# Legendre.net
KiCad netlist of a schematic drawn in Altium Designer
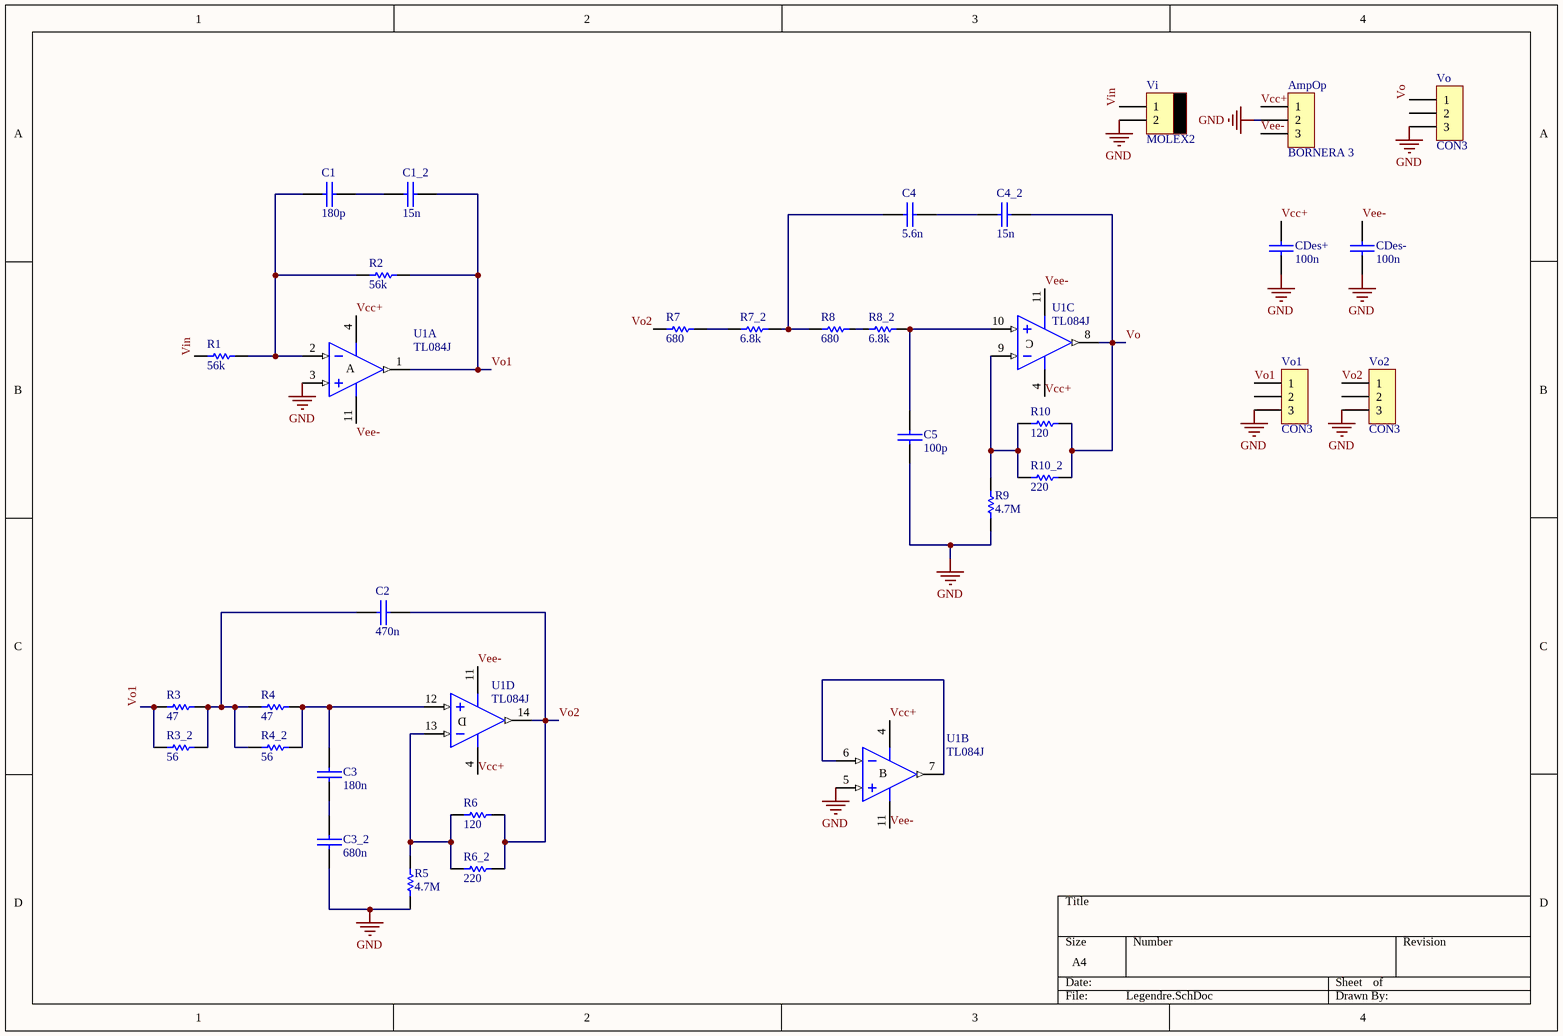
[diagram p0: Legendre.SchDoc]

(export (version "E")
  (design (tool "Eeschema 10.0.6"))
  (components
    (comp (ref "AmpOp")
      (value "BORNERA 3")
      (footprint "BORNERA3")
      (libsource (lib "LIBEBAL") (part "BORNERA 3"))
    )
    (comp (ref "C1") (value "180p") (footprint "0805") (libsource (lib "LIBEBAL") (part "CAP")))
    (comp (ref "C1_2") (value "15n") (footprint "0805") (libsource (lib "LIBEBAL") (part "CAP")))
    (comp (ref "C2") (value "470n") (footprint "0805") (libsource (lib "LIBEBAL") (part "CAP")))
    (comp (ref "C3") (value "180n") (footprint "0805") (libsource (lib "LIBEBAL") (part "CAP")))
    (comp (ref "C3_2") (value "680n") (footprint "CAP100") (libsource (lib "LIBEBAL") (part "CAP")))
    (comp (ref "C4") (value "5.6n") (footprint "0805") (libsource (lib "LIBEBAL") (part "CAP")))
    (comp (ref "C4_2") (value "15n") (footprint "0805") (libsource (lib "LIBEBAL") (part "CAP")))
    (comp (ref "C5") (value "100p") (footprint "CAP100") (libsource (lib "LIBEBAL") (part "CAP")))
    (comp (ref "CDes+") (value "100n") (footprint "CAP100") (libsource (lib "LIBEBAL") (part "CAP")))
    (comp (ref "CDes-") (value "100n") (footprint "CAP100") (libsource (lib "LIBEBAL") (part "CAP")))
    (comp (ref "R1") (value "56k") (footprint "0805") (libsource (lib "LIBEBAL") (part "RES")))
    (comp (ref "R2") (value "56k") (footprint "0805") (libsource (lib "LIBEBAL") (part "RES")))
    (comp (ref "R3") (value "47") (footprint "0805") (libsource (lib "LIBEBAL") (part "RES")))
    (comp (ref "R3_2") (value "56") (footprint "0805") (libsource (lib "LIBEBAL") (part "RES")))
    (comp (ref "R4") (value "47") (footprint "0805") (libsource (lib "LIBEBAL") (part "RES")))
    (comp (ref "R4_2") (value "56") (footprint "0805") (libsource (lib "LIBEBAL") (part "RES")))
    (comp (ref "R5") (value "4.7M") (footprint "0805") (libsource (lib "LIBEBAL") (part "RES")))
    (comp (ref "R6") (value "120") (footprint "0805") (libsource (lib "LIBEBAL") (part "RES")))
    (comp (ref "R6_2") (value "220") (footprint "0805") (libsource (lib "LIBEBAL") (part "RES")))
    (comp (ref "R7") (value "680") (footprint "0805") (libsource (lib "LIBEBAL") (part "RES")))
    (comp (ref "R7_2") (value "6.8k") (footprint "0805") (libsource (lib "LIBEBAL") (part "RES")))
    (comp (ref "R8") (value "680") (footprint "0805") (libsource (lib "LIBEBAL") (part "RES")))
    (comp (ref "R8_2") (value "6.8k") (footprint "0805") (libsource (lib "LIBEBAL") (part "RES")))
    (comp (ref "R9") (value "4.7M") (footprint "0805") (libsource (lib "LIBEBAL") (part "RES")))
    (comp (ref "R10") (value "120") (footprint "0805") (libsource (lib "LIBEBAL") (part "RES")))
    (comp (ref "R10_2") (value "220") (footprint "0805") (libsource (lib "LIBEBAL") (part "RES")))
    (comp (ref "U1")
      (value "TL084J")
      (footprint "J014")
      (description "JFET-Input Operational Amplifier")
      (fields (field (name "PUBLISHER") "Altium Limited"))
      (libsource (lib "TI Operational Amplifier") (part "TL084J"))
    )
    (comp (ref "Vi") (value "MOLEX2") (footprint "MOLEX2") (libsource (lib "LIBEBAL") (part "MOLEX2")))
    (comp (ref "Vo") (value "CON3") (footprint "SIP3") (libsource (lib "LIBEBAL") (part "CON3")))
    (comp (ref "Vo1") (value "CON3") (footprint "SIP3") (libsource (lib "LIBEBAL") (part "CON3")))
    (comp (ref "Vo2") (value "CON3") (footprint "SIP3") (libsource (lib "LIBEBAL") (part "CON3")))
  )
  (nets
    (net (code "1") (name "/Vcc+") (class "Default")
      (node (ref "AmpOp") (pin "1") (pinfunction "1_1") (pintype "passive"))
      (node (ref "CDes+") (pin "1") (pinfunction "1_1") (pintype "passive"))
      (node (ref "U1") (pin "4") (pinfunction "V+_4") (pintype "power_in"))
    )
    (net (code "2") (name "/Vee-") (class "Default")
      (node (ref "AmpOp") (pin "3") (pinfunction "3_3") (pintype "passive"))
      (node (ref "CDes-") (pin "1") (pinfunction "1_1") (pintype "passive"))
      (node (ref "U1") (pin "11") (pinfunction "V-_11") (pintype "power_in"))
    )
    (net (code "3") (name "/Vin") (class "Default")
      (node (ref "R1") (pin "1") (pinfunction "1_1") (pintype "passive"))
      (node (ref "Vi") (pin "1") (pinfunction "1_1") (pintype "passive"))
    )
    (net (code "4") (name "/Vo") (class "Default")
      (node (ref "C4_2") (pin "2") (pinfunction "2_2") (pintype "passive"))
      (node (ref "R10") (pin "2") (pinfunction "2_2") (pintype "passive"))
      (node (ref "R10_2") (pin "2") (pinfunction "2_2") (pintype "passive"))
      (node (ref "U1") (pin "8") (pinfunction "OUT_8") (pintype "output"))
      (node (ref "Vo") (pin "1") (pinfunction "1_1") (pintype "passive"))
    )
    (net (code "5") (name "/Vo1") (class "Default")
      (node (ref "C1_2") (pin "2") (pinfunction "2_2") (pintype "passive"))
      (node (ref "R2") (pin "2") (pinfunction "2_2") (pintype "passive"))
      (node (ref "R3") (pin "1") (pinfunction "1_1") (pintype "passive"))
      (node (ref "R3_2") (pin "1") (pinfunction "1_1") (pintype "passive"))
      (node (ref "U1") (pin "1") (pinfunction "OUT_1") (pintype "output"))
      (node (ref "Vo1") (pin "1") (pinfunction "1_1") (pintype "passive"))
    )
    (net (code "6") (name "/Vo2") (class "Default")
      (node (ref "C2") (pin "2") (pinfunction "2_2") (pintype "passive"))
      (node (ref "R6") (pin "2") (pinfunction "2_2") (pintype "passive"))
      (node (ref "R6_2") (pin "2") (pinfunction "2_2") (pintype "passive"))
      (node (ref "R7") (pin "1") (pinfunction "1_1") (pintype "passive"))
      (node (ref "U1") (pin "14") (pinfunction "OUT_14") (pintype "output"))
      (node (ref "Vo2") (pin "1") (pinfunction "1_1") (pintype "passive"))
    )
    (net (code "7") (name "GND") (class "Default")
      (node (ref "AmpOp") (pin "2") (pinfunction "2_2") (pintype "passive"))
      (node (ref "C3_2") (pin "2") (pinfunction "2_2") (pintype "passive"))
      (node (ref "C5") (pin "2") (pinfunction "2_2") (pintype "passive"))
      (node (ref "CDes+") (pin "2") (pinfunction "2_2") (pintype "passive"))
      (node (ref "CDes-") (pin "2") (pinfunction "2_2") (pintype "passive"))
      (node (ref "R5") (pin "1") (pinfunction "1_1") (pintype "passive"))
      (node (ref "R9") (pin "1") (pinfunction "1_1") (pintype "passive"))
      (node (ref "U1") (pin "3") (pinfunction "IN+_3") (pintype "input"))
      (node (ref "U1") (pin "5") (pinfunction "IN+_5") (pintype "input"))
      (node (ref "Vi") (pin "2") (pinfunction "2_2") (pintype "passive"))
      (node (ref "Vo") (pin "3") (pinfunction "3_3") (pintype "passive"))
      (node (ref "Vo1") (pin "3") (pinfunction "3_3") (pintype "passive"))
      (node (ref "Vo2") (pin "3") (pinfunction "3_3") (pintype "passive"))
    )
    (net (code "8") (name "Net-(C1-Pad2)") (class "Default")
      (node (ref "C1") (pin "2") (pinfunction "2_2") (pintype "passive"))
      (node (ref "C1_2") (pin "1") (pinfunction "1_1") (pintype "passive"))
    )
    (net (code "9") (name "Net-(C2-Pad1)") (class "Default")
      (node (ref "C2") (pin "1") (pinfunction "1_1") (pintype "passive"))
      (node (ref "R3") (pin "2") (pinfunction "2_2") (pintype "passive"))
      (node (ref "R3_2") (pin "2") (pinfunction "2_2") (pintype "passive"))
      (node (ref "R4") (pin "1") (pinfunction "1_1") (pintype "passive"))
      (node (ref "R4_2") (pin "1") (pinfunction "1_1") (pintype "passive"))
    )
    (net (code "10") (name "Net-(C3-Pad2)") (class "Default")
      (node (ref "C3") (pin "2") (pinfunction "2_2") (pintype "passive"))
      (node (ref "C3_2") (pin "1") (pinfunction "1_1") (pintype "passive"))
    )
    (net (code "11") (name "Net-(C4-Pad1)") (class "Default")
      (node (ref "C4") (pin "1") (pinfunction "1_1") (pintype "passive"))
      (node (ref "R7_2") (pin "2") (pinfunction "2_2") (pintype "passive"))
      (node (ref "R8") (pin "1") (pinfunction "1_1") (pintype "passive"))
    )
    (net (code "12") (name "Net-(C4-Pad2)") (class "Default")
      (node (ref "C4") (pin "2") (pinfunction "2_2") (pintype "passive"))
      (node (ref "C4_2") (pin "1") (pinfunction "1_1") (pintype "passive"))
    )
    (net (code "13") (name "Net-(R7-Pad2)") (class "Default")
      (node (ref "R7") (pin "2") (pinfunction "2_2") (pintype "passive"))
      (node (ref "R7_2") (pin "1") (pinfunction "1_1") (pintype "passive"))
    )
    (net (code "14") (name "Net-(R8-Pad2)") (class "Default")
      (node (ref "R8") (pin "2") (pinfunction "2_2") (pintype "passive"))
      (node (ref "R8_2") (pin "1") (pinfunction "1_1") (pintype "passive"))
    )
    (net (code "15") (name "Net-(U1A-IN-)") (class "Default")
      (node (ref "C1") (pin "1") (pinfunction "1_1") (pintype "passive"))
      (node (ref "R1") (pin "2") (pinfunction "2_2") (pintype "passive"))
      (node (ref "R2") (pin "1") (pinfunction "1_1") (pintype "passive"))
      (node (ref "U1") (pin "2") (pinfunction "IN-_2") (pintype "input"))
    )
    (net (code "16") (name "Net-(U1B-IN-)") (class "Default")
      (node (ref "U1") (pin "6") (pinfunction "IN-_6") (pintype "input"))
      (node (ref "U1") (pin "7") (pinfunction "OUT_7") (pintype "output"))
    )
    (net (code "17") (name "Net-(U1C-IN+)") (class "Default")
      (node (ref "C5") (pin "1") (pinfunction "1_1") (pintype "passive"))
      (node (ref "R8_2") (pin "2") (pinfunction "2_2") (pintype "passive"))
      (node (ref "U1") (pin "10") (pinfunction "IN+_10") (pintype "input"))
    )
    (net (code "18") (name "Net-(U1C-IN-)") (class "Default")
      (node (ref "R10") (pin "1") (pinfunction "1_1") (pintype "passive"))
      (node (ref "R10_2") (pin "1") (pinfunction "1_1") (pintype "passive"))
      (node (ref "R9") (pin "2") (pinfunction "2_2") (pintype "passive"))
      (node (ref "U1") (pin "9") (pinfunction "IN-_9") (pintype "input"))
    )
    (net (code "19") (name "Net-(U1D-IN+)") (class "Default")
      (node (ref "C3") (pin "1") (pinfunction "1_1") (pintype "passive"))
      (node (ref "R4") (pin "2") (pinfunction "2_2") (pintype "passive"))
      (node (ref "R4_2") (pin "2") (pinfunction "2_2") (pintype "passive"))
      (node (ref "U1") (pin "12") (pinfunction "IN+_12") (pintype "input"))
    )
    (net (code "20") (name "Net-(U1D-IN-)") (class "Default")
      (node (ref "R5") (pin "2") (pinfunction "2_2") (pintype "passive"))
      (node (ref "R6") (pin "1") (pinfunction "1_1") (pintype "passive"))
      (node (ref "R6_2") (pin "1") (pinfunction "1_1") (pintype "passive"))
      (node (ref "U1") (pin "13") (pinfunction "IN-_13") (pintype "input"))
    )
    (net (code "21") (name "unconnected-(Vo-Pad2)") (class "Default")
      (node (ref "Vo") (pin "2") (pinfunction "2_2") (pintype "passive"))
    )
    (net (code "22") (name "unconnected-(Vo1-Pad2)") (class "Default")
      (node (ref "Vo1") (pin "2") (pinfunction "2_2") (pintype "passive"))
    )
    (net (code "23") (name "unconnected-(Vo2-Pad2)") (class "Default")
      (node (ref "Vo2") (pin "2") (pinfunction "2_2") (pintype "passive"))
    )
  )
)
